# REG113-5_sch.net
KiCad netlist of a schematic drawn in Altium Designer
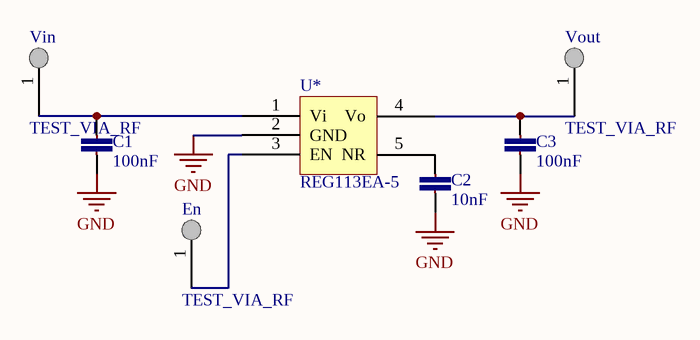
[diagram p0: REG113-5_sch.SchDoc]

(export (version "E")
  (design (tool "Eeschema 10.0.6"))
  (components
    (comp (ref "C1")
      (value "100nF")
      (footprint "0402-CAP")
      (description "CAP CER 0.1UF 50V 10% X7R 0402")
      (fields (field (name "PART NO") "C1005X7R1H104K050BB"))
      (libsource (lib "IMBEL") (part "CAPACITOR"))
    )
    (comp (ref "C2")
      (value "10nF")
      (footprint "0402-CAP")
      (description "CAP CER 10000PF 25V 5% X7R 0402")
      (fields (field (name "PART NO") "GRM155R71E103JA01J"))
      (libsource (lib "IMBEL") (part "CAPACITOR"))
    )
    (comp (ref "C3")
      (value "100nF")
      (footprint "0402-CAP")
      (description "CAP CER 0.1UF 50V 10% X7R 0402")
      (fields (field (name "PART NO") "C1005X7R1H104K050BB"))
      (libsource (lib "IMBEL") (part "CAPACITOR"))
    )
    (comp (ref "En")
      (value "TEST_VIA_RF")
      (footprint "New footprint 1")
      (description "Test VIA for RF circuits")
      (libsource (lib "IMBEL") (part "TEST_VIA"))
    )
    (comp (ref "U*")
      (value "REG113EA-5")
      (footprint "SOT95P280X145-5N")
      (description "IC REG LINEAR 5.0V 400MA 8VSSOP")
      (libsource (lib "IMBEL") (part "REG113"))
    )
    (comp (ref "Vin")
      (value "TEST_VIA_RF")
      (footprint "New footprint 1")
      (description "Test VIA for RF circuits")
      (libsource (lib "IMBEL") (part "TEST_VIA"))
    )
    (comp (ref "Vout")
      (value "TEST_VIA_RF")
      (footprint "New footprint 1")
      (description "Test VIA for RF circuits")
      (libsource (lib "IMBEL") (part "TEST_VIA"))
    )
  )
  (nets
    (net (code "1") (name "GND") (class "Default")
      (node (ref "C1") (pin "2") (pinfunction "2_2") (pintype "passive"))
      (node (ref "C2") (pin "2") (pinfunction "2_2") (pintype "passive"))
      (node (ref "C3") (pin "2") (pinfunction "2_2") (pintype "passive"))
      (node (ref "U*") (pin "2") (pinfunction "GND_2") (pintype "passive"))
    )
    (net (code "2") (name "Net-(U*-EN)") (class "Default")
      (node (ref "En") (pin "1") (pinfunction "1_1") (pintype "passive"))
      (node (ref "U*") (pin "3") (pinfunction "EN_3") (pintype "passive"))
    )
    (net (code "3") (name "Net-(U*-NR)") (class "Default")
      (node (ref "C2") (pin "1") (pinfunction "1_1") (pintype "passive"))
      (node (ref "U*") (pin "5") (pinfunction "NR_5") (pintype "passive"))
    )
    (net (code "4") (name "Net-(U*-Vi)") (class "Default")
      (node (ref "C1") (pin "1") (pinfunction "1_1") (pintype "passive"))
      (node (ref "U*") (pin "1") (pinfunction "Vi_1") (pintype "passive"))
      (node (ref "Vin") (pin "1") (pinfunction "1_1") (pintype "passive"))
    )
    (net (code "5") (name "Net-(U*-Vo)") (class "Default")
      (node (ref "C3") (pin "1") (pinfunction "1_1") (pintype "passive"))
      (node (ref "U*") (pin "4") (pinfunction "Vo_4") (pintype "passive"))
      (node (ref "Vout") (pin "1") (pinfunction "1_1") (pintype "passive"))
    )
  )
)
